# 19V_Converter.net
KiCad netlist of a schematic drawn in Altium Designer
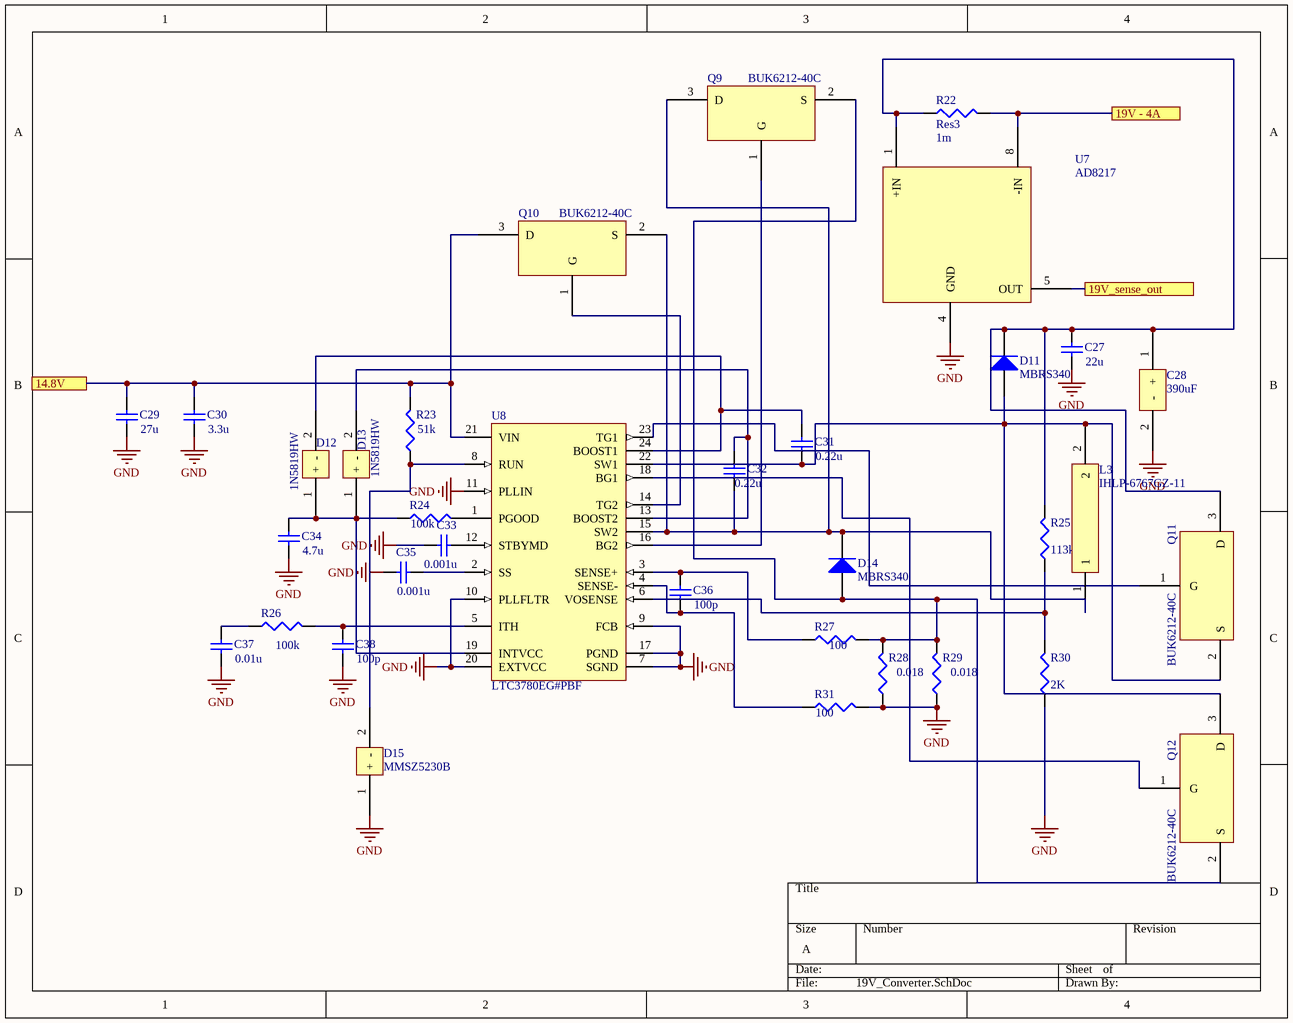
[diagram p0: 19V_Converter.SchDoc]

(export (version "E")
  (design (tool "Eeschema 10.0.6"))
  (components
    (comp (ref "C27")
      (value "22u")
      (footprint "C1206")
      (description "Capacitor (Semiconductor SIM Model)")
      (fields (field (name "Comment") "Cap Semi") (field (name "PUBLISHER") "Altium Limited"))
      (libsource (lib "Miscellaneous Devices") (part "Cap Semi"))
    )
    (comp (ref "C28")
      (value "390uF")
      (footprint "PCV1E391MCL2GS")
      (description "Aluminum Capacitor")
      (libsource (lib "Integrated_Library") (part "PCV1E391MCL2GS"))
    )
    (comp (ref "C29")
      (value "27u")
      (footprint "C1206")
      (description "Capacitor (Semiconductor SIM Model)")
      (fields (field (name "Comment") "Cap Semi") (field (name "PUBLISHER") "Altium Limited"))
      (libsource (lib "Miscellaneous Devices") (part "Cap Semi"))
    )
    (comp (ref "C30")
      (value "3.3u")
      (footprint "C1206")
      (description "Capacitor (Semiconductor SIM Model)")
      (fields (field (name "Comment") "Cap Semi") (field (name "PUBLISHER") "Altium Limited"))
      (libsource (lib "Miscellaneous Devices") (part "Cap Semi"))
    )
    (comp (ref "C31")
      (value "0.22u")
      (footprint "C1206")
      (description "Capacitor (Semiconductor SIM Model)")
      (fields (field (name "Comment") "Cap Semi") (field (name "PUBLISHER") "Altium Limited"))
      (libsource (lib "Miscellaneous Devices") (part "Cap Semi"))
    )
    (comp (ref "C32")
      (value "0.22u")
      (footprint "C1206")
      (description "Capacitor (Semiconductor SIM Model)")
      (fields (field (name "Comment") "Cap Semi") (field (name "PUBLISHER") "Altium Limited"))
      (libsource (lib "Miscellaneous Devices") (part "Cap Semi"))
    )
    (comp (ref "C33")
      (value "0.001u")
      (footprint "C1206")
      (description "Capacitor (Semiconductor SIM Model)")
      (fields (field (name "Comment") "Cap Semi") (field (name "PUBLISHER") "Altium Limited"))
      (libsource (lib "Miscellaneous Devices") (part "Cap Semi"))
    )
    (comp (ref "C34")
      (value "4.7u")
      (footprint "C1206")
      (description "Capacitor (Semiconductor SIM Model)")
      (fields (field (name "Comment") "Cap Semi") (field (name "PUBLISHER") "Altium Limited"))
      (libsource (lib "Miscellaneous Devices") (part "Cap Semi"))
    )
    (comp (ref "C35")
      (value "0.001u")
      (footprint "C1206")
      (description "Capacitor (Semiconductor SIM Model)")
      (fields (field (name "Comment") "Cap Semi") (field (name "PUBLISHER") "Altium Limited"))
      (libsource (lib "Miscellaneous Devices") (part "Cap Semi"))
    )
    (comp (ref "C36")
      (value "100p")
      (footprint "C1206")
      (description "Capacitor (Semiconductor SIM Model)")
      (fields (field (name "Comment") "Cap Semi") (field (name "PUBLISHER") "Altium Limited"))
      (libsource (lib "Miscellaneous Devices") (part "Cap Semi"))
    )
    (comp (ref "C37")
      (value "0.01u")
      (footprint "C1206")
      (description "Capacitor (Semiconductor SIM Model)")
      (fields (field (name "Comment") "Cap Semi") (field (name "PUBLISHER") "Altium Limited"))
      (libsource (lib "Miscellaneous Devices") (part "Cap Semi"))
    )
    (comp (ref "C38")
      (value "100p")
      (footprint "C1206")
      (description "Capacitor (Semiconductor SIM Model)")
      (fields (field (name "Comment") "Cap Semi") (field (name "PUBLISHER") "Altium Limited"))
      (libsource (lib "Miscellaneous Devices") (part "Cap Semi"))
    )
    (comp (ref "D11")
      (value "MBRS340")
      (footprint "SMC")
      (description "Default Diode")
      (fields (field (name "PUBLISHER") "Altium Limited"))
      (libsource (lib "Miscellaneous Devices") (part "Diode"))
    )
    (comp (ref "D12")
      (value "1N5819HW")
      (footprint "1N5819HW")
      (description "1A Schottky Barrier Rectifier")
      (libsource (lib "Integrated_Library") (part "1N5819HW"))
    )
    (comp (ref "D13")
      (value "1N5819HW")
      (footprint "1N5819HW")
      (description "1A Schottky Barrier Rectifier")
      (libsource (lib "Integrated_Library") (part "1N5819HW"))
    )
    (comp (ref "D14")
      (value "MBRS340")
      (footprint "SMC")
      (description "Default Diode")
      (fields (field (name "PUBLISHER") "Altium Limited"))
      (libsource (lib "Miscellaneous Devices") (part "Diode"))
    )
    (comp (ref "D15")
      (value "MMSZ5230B")
      (footprint "MMSZ5230B")
      (description "Zener Diode")
      (libsource (lib "Integrated_Library") (part "MMSZ5230B"))
    )
    (comp (ref "L3")
      (value "IHLP-6767GZ-11")
      (footprint "IHLP-6767GZ-11")
      (description "Inductor")
      (libsource (lib "Power_Board_Parts_Library_Final") (part "IHLP-6767GZ-11"))
    )
    (comp (ref "Q9")
      (value "BUK6212-40C")
      (footprint "BUK6212-40C")
      (description "N-Channel TrenchMOS Intermediate Level FET")
      (libsource (lib "") (part "BUK6212-40C_1"))
    )
    (comp (ref "Q10")
      (value "BUK6212-40C")
      (footprint "BUK6212-40C")
      (description "N-Channel TrenchMOS Intermediate Level FET")
      (libsource (lib "") (part "BUK6212-40C_1"))
    )
    (comp (ref "Q11")
      (value "BUK6212-40C")
      (footprint "BUK6212-40C")
      (description "N-Channel TrenchMOS Intermediate Level FET")
      (libsource (lib "Integrated_Library") (part "BUK6212-40C"))
    )
    (comp (ref "Q12")
      (value "BUK6212-40C")
      (footprint "BUK6212-40C")
      (description "N-Channel TrenchMOS Intermediate Level FET")
      (libsource (lib "Integrated_Library") (part "BUK6212-40C"))
    )
    (comp (ref "R22")
      (value "Res3")
      (footprint "14-1210")
      (description "Resistor")
      (fields (field (name "ALTIUM_VALUE") "1m") (field (name "PUBLISHER") "Altium Limited"))
      (libsource (lib "Miscellaneous Devices") (part "Res3"))
    )
    (comp (ref "R23")
      (value "51k")
      (footprint "J1-0603")
      (description "Resistor")
      (fields (field (name "Comment") "Res3") (field (name "PUBLISHER") "Altium Limited"))
      (libsource (lib "Miscellaneous Devices") (part "Res3"))
    )
    (comp (ref "R24")
      (value "100k")
      (footprint "J1-0603")
      (description "Resistor")
      (fields (field (name "Comment") "Res3") (field (name "PUBLISHER") "Altium Limited"))
      (libsource (lib "Miscellaneous Devices") (part "Res3"))
    )
    (comp (ref "R25")
      (value "113k")
      (footprint "J1-0603")
      (description "Resistor")
      (fields (field (name "Comment") "Res3") (field (name "PUBLISHER") "Altium Limited"))
      (libsource (lib "Miscellaneous Devices") (part "Res3"))
    )
    (comp (ref "R26")
      (value "100k")
      (footprint "J1-0603")
      (description "Resistor")
      (fields (field (name "Comment") "Res3") (field (name "PUBLISHER") "Altium Limited"))
      (libsource (lib "Miscellaneous Devices") (part "Res3"))
    )
    (comp (ref "R27")
      (value "100")
      (footprint "J1-0603")
      (description "Resistor")
      (fields (field (name "Comment") "Res3") (field (name "PUBLISHER") "Altium Limited"))
      (libsource (lib "Miscellaneous Devices") (part "Res3"))
    )
    (comp (ref "R28")
      (value "0.018")
      (footprint "14-1210")
      (description "Resistor")
      (fields (field (name "Comment") "Res3") (field (name "PUBLISHER") "Altium Limited"))
      (libsource (lib "Miscellaneous Devices") (part "Res3"))
    )
    (comp (ref "R29")
      (value "0.018")
      (footprint "14-1210")
      (description "Resistor")
      (fields (field (name "Comment") "Res3") (field (name "PUBLISHER") "Altium Limited"))
      (libsource (lib "Miscellaneous Devices") (part "Res3"))
    )
    (comp (ref "R30")
      (value "2K")
      (footprint "J1-0603")
      (description "Resistor")
      (fields (field (name "Comment") "Res3") (field (name "PUBLISHER") "Altium Limited"))
      (libsource (lib "Miscellaneous Devices") (part "Res3"))
    )
    (comp (ref "R31")
      (value "100")
      (footprint "J1-0603")
      (description "Resistor")
      (fields (field (name "Comment") "Res3") (field (name "PUBLISHER") "Altium Limited"))
      (libsource (lib "Miscellaneous Devices") (part "Res3"))
    )
    (comp (ref "U7")
      (value "AD8217")
      (footprint "AD8217")
      (description "Current Shunt Moniter")
      (libsource (lib "Integrated_Library") (part "AD8217"))
    )
    (comp (ref "U8")
      (value "LTC3780EG#PBF")
      (footprint "LTC3780 24-Leaqd Plastic SSOP")
      (fields (field (name "MANUFACTURER") "Linear Technology"))
      (libsource (lib "Integrated_Library") (part "LTC3780EG#PBF"))
    )
  )
  (nets
    (net (code "1") (name "/14.8V") (class "Default")
      (node (ref "C29") (pin "2") (pinfunction "2_2") (pintype "passive"))
      (node (ref "C30") (pin "2") (pinfunction "2_2") (pintype "passive"))
      (node (ref "Q10") (pin "3") (pinfunction "D_3") (pintype "passive"))
      (node (ref "R23") (pin "2") (pinfunction "2_2") (pintype "passive"))
      (node (ref "U8") (pin "21") (pinfunction "VIN_21") (pintype "power_in"))
    )
    (net (code "2") (name "/19V - 4A") (class "Default")
      (node (ref "R22") (pin "2") (pinfunction "2_2") (pintype "passive"))
      (node (ref "U7") (pin "8") (pinfunction "-IN_8") (pintype "passive"))
    )
    (net (code "3") (name "/19V_sense_out") (class "Default")
      (node (ref "U7") (pin "5") (pinfunction "OUT_5") (pintype "passive"))
    )
    (net (code "4") (name "GND") (class "Default")
      (node (ref "C27") (pin "1") (pinfunction "1_1") (pintype "passive"))
      (node (ref "C28") (pin "2") (pinfunction "-_2") (pintype "passive"))
      (node (ref "C29") (pin "1") (pinfunction "1_1") (pintype "passive"))
      (node (ref "C30") (pin "1") (pinfunction "1_1") (pintype "passive"))
      (node (ref "C33") (pin "1") (pinfunction "1_1") (pintype "passive"))
      (node (ref "C34") (pin "1") (pinfunction "1_1") (pintype "passive"))
      (node (ref "C35") (pin "1") (pinfunction "1_1") (pintype "passive"))
      (node (ref "C37") (pin "1") (pinfunction "1_1") (pintype "passive"))
      (node (ref "C38") (pin "1") (pinfunction "1_1") (pintype "passive"))
      (node (ref "D15") (pin "1") (pinfunction "+_1") (pintype "passive"))
      (node (ref "R28") (pin "1") (pinfunction "1_1") (pintype "passive"))
      (node (ref "R29") (pin "1") (pinfunction "1_1") (pintype "passive"))
      (node (ref "R30") (pin "1") (pinfunction "1_1") (pintype "passive"))
      (node (ref "R31") (pin "2") (pinfunction "2_2") (pintype "passive"))
      (node (ref "U7") (pin "4") (pinfunction "GND_4") (pintype "passive"))
      (node (ref "U8") (pin "10") (pinfunction "PLLFLTR_10") (pintype "input"))
      (node (ref "U8") (pin "11") (pinfunction "PLLIN_11") (pintype "input"))
      (node (ref "U8") (pin "17") (pinfunction "PGND_17") (pintype "power_in"))
      (node (ref "U8") (pin "20") (pinfunction "EXTVCC_20") (pintype "power_in"))
      (node (ref "U8") (pin "7") (pinfunction "SGND_7") (pintype "power_in"))
      (node (ref "U8") (pin "9") (pinfunction "FCB_9") (pintype "input"))
    )
    (net (code "5") (name "Net-(C28-+)") (class "Default")
      (node (ref "C27") (pin "2") (pinfunction "2_2") (pintype "passive"))
      (node (ref "C28") (pin "1") (pinfunction "+_1") (pintype "passive"))
      (node (ref "D11") (pin "2") (pinfunction "K_2") (pintype "passive"))
      (node (ref "Q11") (pin "3") (pinfunction "D_3") (pintype "passive"))
      (node (ref "R22") (pin "1") (pinfunction "1_1") (pintype "passive"))
      (node (ref "R25") (pin "2") (pinfunction "2_2") (pintype "passive"))
      (node (ref "U7") (pin "1") (pinfunction "+IN_1") (pintype "passive"))
    )
    (net (code "6") (name "Net-(C37-Pad2)") (class "Default")
      (node (ref "C37") (pin "2") (pinfunction "2_2") (pintype "passive"))
      (node (ref "R26") (pin "1") (pinfunction "1_1") (pintype "passive"))
    )
    (net (code "7") (name "Net-(D11-A)") (class "Default")
      (node (ref "C31") (pin "1") (pinfunction "1_1") (pintype "passive"))
      (node (ref "D11") (pin "1") (pinfunction "A_1") (pintype "passive"))
      (node (ref "L3") (pin "2") (pinfunction "2_2") (pintype "passive"))
      (node (ref "Q11") (pin "2") (pinfunction "S_2") (pintype "passive"))
      (node (ref "Q12") (pin "3") (pinfunction "D_3") (pintype "passive"))
      (node (ref "U8") (pin "22") (pinfunction "SW1_22") (pintype "passive"))
    )
    (net (code "8") (name "Net-(D12-+)") (class "Default")
      (node (ref "C34") (pin "2") (pinfunction "2_2") (pintype "passive"))
      (node (ref "D12") (pin "1") (pinfunction "+_1") (pintype "passive"))
      (node (ref "D13") (pin "1") (pinfunction "+_1") (pintype "passive"))
      (node (ref "R24") (pin "1") (pinfunction "1_1") (pintype "passive"))
      (node (ref "U8") (pin "19") (pinfunction "INTVCC_19") (pintype "power_in"))
    )
    (net (code "9") (name "Net-(D12--)") (class "Default")
      (node (ref "C31") (pin "2") (pinfunction "2_2") (pintype "passive"))
      (node (ref "D12") (pin "2") (pinfunction "-_2") (pintype "passive"))
      (node (ref "U8") (pin "24") (pinfunction "BOOST1_24") (pintype "passive"))
    )
    (net (code "10") (name "Net-(D13--)") (class "Default")
      (node (ref "C32") (pin "2") (pinfunction "2_2") (pintype "passive"))
      (node (ref "D13") (pin "2") (pinfunction "-_2") (pintype "passive"))
      (node (ref "U8") (pin "13") (pinfunction "BOOST2_13") (pintype "passive"))
    )
    (net (code "11") (name "Net-(D14-A)") (class "Default")
      (node (ref "D14") (pin "1") (pinfunction "A_1") (pintype "passive"))
      (node (ref "Q12") (pin "2") (pinfunction "S_2") (pintype "passive"))
      (node (ref "Q9") (pin "2") (pinfunction "S_2") (pintype "passive"))
      (node (ref "R27") (pin "2") (pinfunction "2_2") (pintype "passive"))
      (node (ref "R28") (pin "2") (pinfunction "2_2") (pintype "passive"))
      (node (ref "R29") (pin "2") (pinfunction "2_2") (pintype "passive"))
    )
    (net (code "12") (name "Net-(D14-K)") (class "Default")
      (node (ref "C32") (pin "1") (pinfunction "1_1") (pintype "passive"))
      (node (ref "D14") (pin "2") (pinfunction "K_2") (pintype "passive"))
      (node (ref "L3") (pin "1") (pinfunction "1_1") (pintype "passive"))
      (node (ref "Q10") (pin "2") (pinfunction "S_2") (pintype "passive"))
      (node (ref "Q9") (pin "3") (pinfunction "D_3") (pintype "passive"))
      (node (ref "U8") (pin "15") (pinfunction "SW2_15") (pintype "passive"))
    )
    (net (code "13") (name "Net-(D15--)") (class "Default")
      (node (ref "D15") (pin "2") (pinfunction "-_2") (pintype "passive"))
      (node (ref "R23") (pin "1") (pinfunction "1_1") (pintype "passive"))
      (node (ref "U8") (pin "8") (pinfunction "RUN_8") (pintype "input"))
    )
    (net (code "14") (name "Net-(Q9-G)") (class "Default")
      (node (ref "Q9") (pin "1") (pinfunction "G_1") (pintype "passive"))
      (node (ref "U8") (pin "16") (pinfunction "BG2_16") (pintype "output"))
    )
    (net (code "15") (name "Net-(Q10-G)") (class "Default")
      (node (ref "Q10") (pin "1") (pinfunction "G_1") (pintype "passive"))
      (node (ref "U8") (pin "14") (pinfunction "TG2_14") (pintype "output"))
    )
    (net (code "16") (name "Net-(Q11-G)") (class "Default")
      (node (ref "Q11") (pin "1") (pinfunction "G_1") (pintype "passive"))
      (node (ref "U8") (pin "23") (pinfunction "TG1_23") (pintype "output"))
    )
    (net (code "17") (name "Net-(Q12-G)") (class "Default")
      (node (ref "Q12") (pin "1") (pinfunction "G_1") (pintype "passive"))
      (node (ref "U8") (pin "18") (pinfunction "BG1_18") (pintype "output"))
    )
    (net (code "18") (name "Net-(U8-ITH)") (class "Default")
      (node (ref "C38") (pin "2") (pinfunction "2_2") (pintype "passive"))
      (node (ref "R26") (pin "2") (pinfunction "2_2") (pintype "passive"))
      (node (ref "U8") (pin "5") (pinfunction "ITH_5") (pintype "passive"))
    )
    (net (code "19") (name "Net-(U8-PGOOD)") (class "Default")
      (node (ref "R24") (pin "2") (pinfunction "2_2") (pintype "passive"))
      (node (ref "U8") (pin "1") (pinfunction "PGOOD_1") (pintype "open_collector"))
    )
    (net (code "20") (name "Net-(U8-SENSE+)") (class "Default")
      (node (ref "C36") (pin "2") (pinfunction "2_2") (pintype "passive"))
      (node (ref "R27") (pin "1") (pinfunction "1_1") (pintype "passive"))
      (node (ref "U8") (pin "3") (pinfunction "SENSE+_3") (pintype "input"))
    )
    (net (code "21") (name "Net-(U8-SENSE-)") (class "Default")
      (node (ref "C36") (pin "1") (pinfunction "1_1") (pintype "passive"))
      (node (ref "R31") (pin "1") (pinfunction "1_1") (pintype "passive"))
      (node (ref "U8") (pin "4") (pinfunction "SENSE-_4") (pintype "input"))
    )
    (net (code "22") (name "Net-(U8-SS)") (class "Default")
      (node (ref "C35") (pin "2") (pinfunction "2_2") (pintype "passive"))
      (node (ref "U8") (pin "2") (pinfunction "SS_2") (pintype "input"))
    )
    (net (code "23") (name "Net-(U8-STBYMD)") (class "Default")
      (node (ref "C33") (pin "2") (pinfunction "2_2") (pintype "passive"))
      (node (ref "U8") (pin "12") (pinfunction "STBYMD_12") (pintype "input"))
    )
    (net (code "24") (name "Net-(U8-VOSENSE)") (class "Default")
      (node (ref "R25") (pin "1") (pinfunction "1_1") (pintype "passive"))
      (node (ref "R30") (pin "2") (pinfunction "2_2") (pintype "passive"))
      (node (ref "U8") (pin "6") (pinfunction "VOSENSE_6") (pintype "input"))
    )
  )
)
